# CHIP_tzatziffy_v7.net
KiCad netlist of a schematic drawn in EAGLE
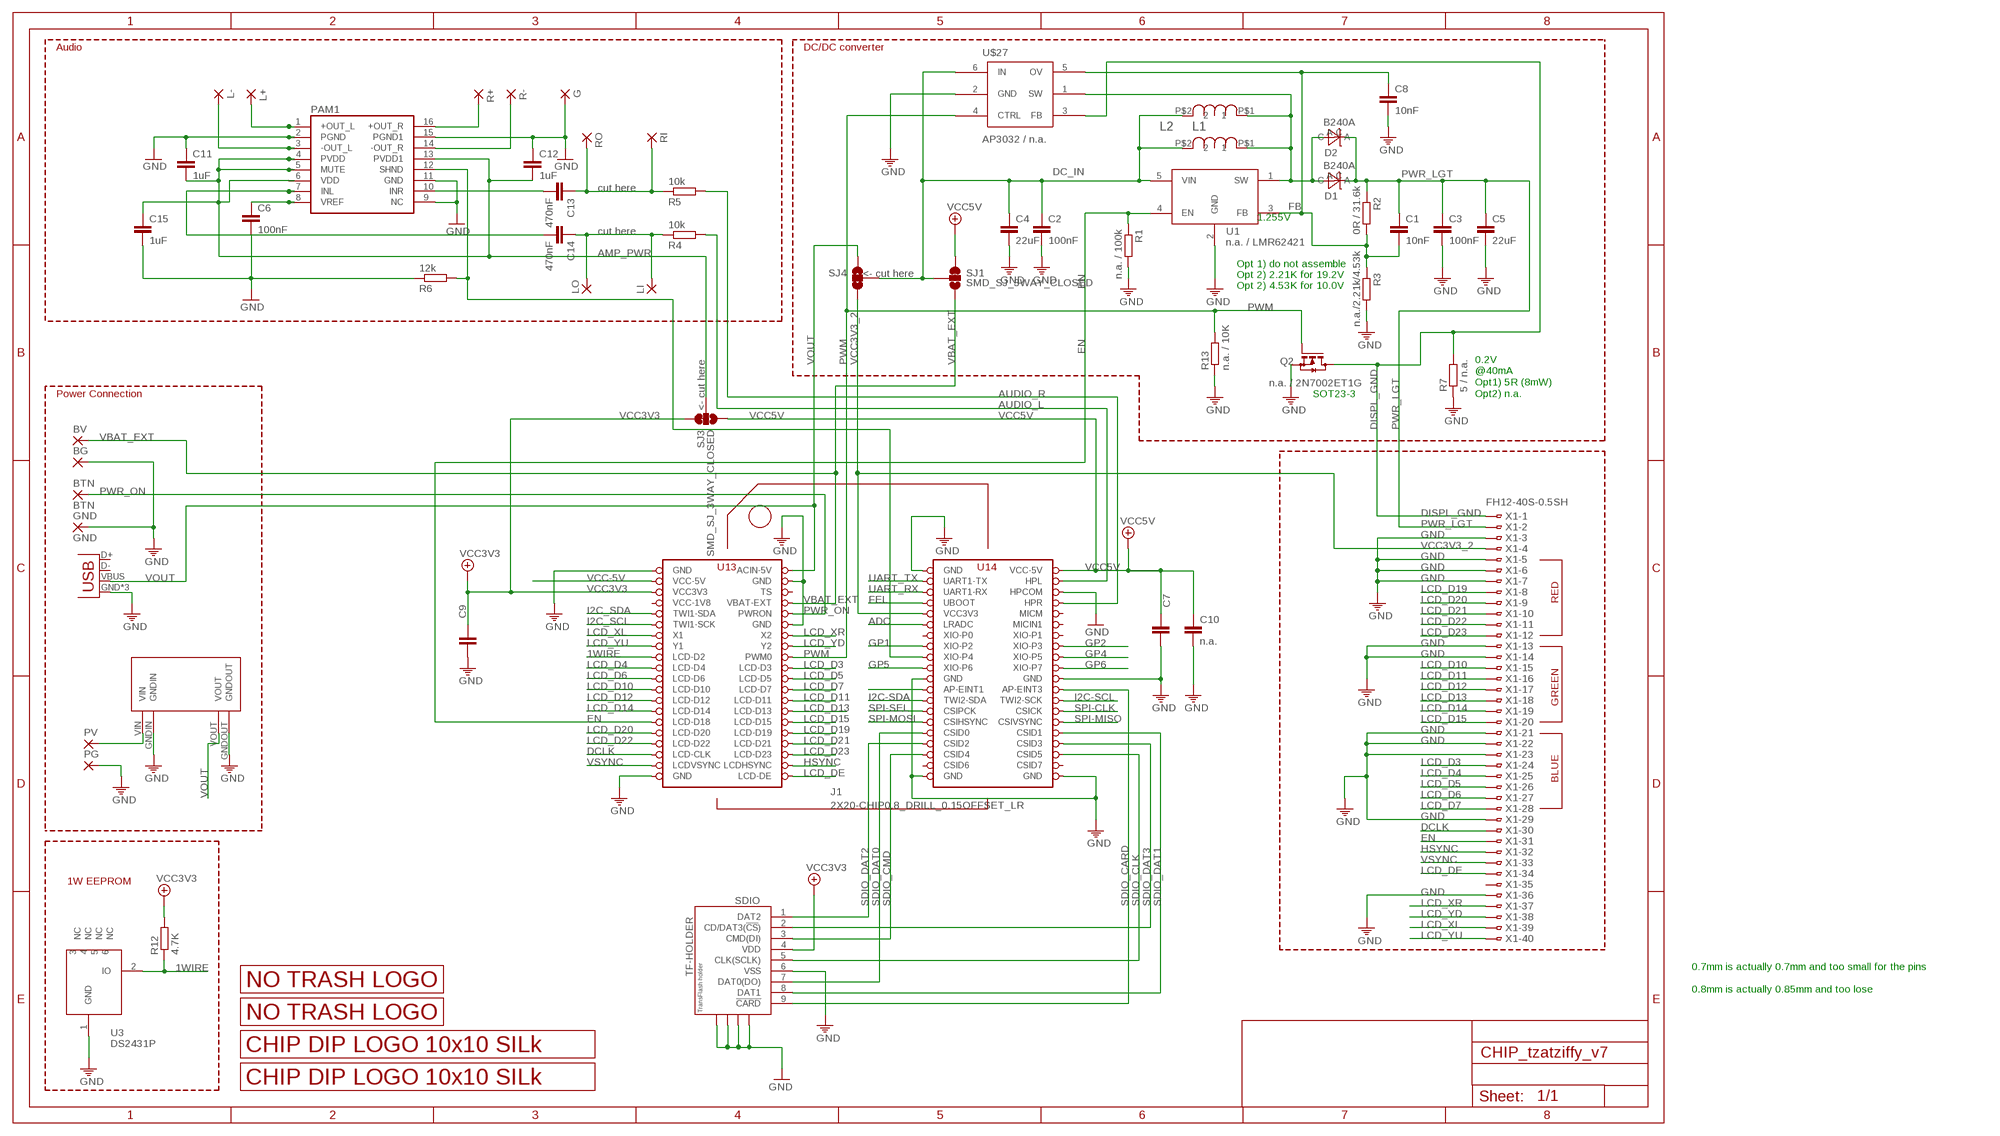
[diagram p0: schematic, sheet 1]

(export (version "E")
  (design (tool "Eeschema 10.0.6"))
  (components
    (comp (ref "BG")
      (value "1,6/0,8")
      (footprint "eagle-import:1,6_0,8")
      (libsource (lib "eagle-import") (part "1,6/0,8"))
    )
    (comp (ref "BTN")
      (value "BTN")
      (footprint "eagle-import:SMD1,27-2,54")
      (libsource (lib "eagle-import") (part "SMD2"))
    )
    (comp (ref "BV")
      (value "1,6/0,8")
      (footprint "eagle-import:1,6_0,8")
      (libsource (lib "eagle-import") (part "1,6/0,8"))
    )
    (comp (ref "C1")
      (value "10nF")
      (footprint "eagle-import:C0805")
      (libsource (lib "eagle-import") (part "C-EUC0805"))
    )
    (comp (ref "C2")
      (value "100nF")
      (footprint "eagle-import:C0805")
      (libsource (lib "eagle-import") (part "C-EUC0805"))
    )
    (comp (ref "C3")
      (value "100nF")
      (footprint "eagle-import:C0805")
      (libsource (lib "eagle-import") (part "C-EUC0805"))
    )
    (comp (ref "C4")
      (value "22uF")
      (footprint "eagle-import:C1206")
      (libsource (lib "eagle-import") (part "C-EUC1206"))
    )
    (comp (ref "C5")
      (value "22uF")
      (footprint "eagle-import:C1206")
      (libsource (lib "eagle-import") (part "C-EUC1206"))
    )
    (comp (ref "C6")
      (value "100nF")
      (footprint "eagle-import:C0805")
      (libsource (lib "eagle-import") (part "C-EUC0805"))
    )
    (comp (ref "C7")
      (value "n.a.")
      (footprint "eagle-import:C0805")
      (libsource (lib "eagle-import") (part "C-EUC0805"))
    )
    (comp (ref "C8")
      (value "10nF")
      (footprint "eagle-import:C0805")
      (libsource (lib "eagle-import") (part "C-EUC0805"))
    )
    (comp (ref "C9")
      (value "n.a.")
      (footprint "eagle-import:C0805")
      (libsource (lib "eagle-import") (part "C-EUC0805"))
    )
    (comp (ref "C10")
      (value "n.a.")
      (footprint "eagle-import:C0805")
      (libsource (lib "eagle-import") (part "C-EUC0805"))
    )
    (comp (ref "C11")
      (value "1uF")
      (footprint "eagle-import:C0805")
      (libsource (lib "eagle-import") (part "C-EUC0805"))
    )
    (comp (ref "C12")
      (value "1uF")
      (footprint "eagle-import:C0805")
      (libsource (lib "eagle-import") (part "C-EUC0805"))
    )
    (comp (ref "C13")
      (value "470nF")
      (footprint "eagle-import:C0805")
      (libsource (lib "eagle-import") (part "C-EUC0805"))
    )
    (comp (ref "C14")
      (value "470nF")
      (footprint "eagle-import:C0805")
      (libsource (lib "eagle-import") (part "C-EUC0805"))
    )
    (comp (ref "C15")
      (value "1uF")
      (footprint "eagle-import:C0805")
      (libsource (lib "eagle-import") (part "C-EUC0805"))
    )
    (comp (ref "D1")
      (value "B240A")
      (footprint "eagle-import:DO-214AC")
      (fields (field (name "MFG") "DIGIKEY") (field (name "VENDOR_PART_NUMBER") "B240A-13-F"))
      (libsource (lib "eagle-import") (part "DIODE_SCHTKY_B240"))
    )
    (comp (ref "D2")
      (value "B240A")
      (footprint "eagle-import:DO-214AC")
      (fields (field (name "MFG") "DIGIKEY") (field (name "VENDOR_PART_NUMBER") "B240A-13-F"))
      (libsource (lib "eagle-import") (part "DIODE_SCHTKY_B240"))
    )
    (comp (ref "G")
      (value "1,6/0,8")
      (footprint "eagle-import:1,6_0,8")
      (libsource (lib "eagle-import") (part "1,6/0,8"))
    )
    (comp (ref "GND")
      (value "GND")
      (footprint "eagle-import:SMD1,27-2,54")
      (libsource (lib "eagle-import") (part "SMD2"))
    )
    (comp (ref "J1")
      (value "2X20-CHIP0.8_DRILL_0.15OFFSET_LR")
      (footprint "eagle-import:2X20CHIP_0.15MM_OFFSET_TH_08")
      (libsource (lib "eagle-import") (part "2X20-CHIP0.8_DRILL_0.15OFFSET_LR"))
    )
    (comp (ref "L+")
      (value "1,6/0,8")
      (footprint "eagle-import:1,6_0,8")
      (libsource (lib "eagle-import") (part "1,6/0,8"))
    )
    (comp (ref "L-")
      (value "1,6/0,8")
      (footprint "eagle-import:1,6_0,8")
      (libsource (lib "eagle-import") (part "1,6/0,8"))
    )
    (comp (ref "L1")
      (value "SRN6045-100M")
      (footprint "eagle-import:SRN6045")
      (fields (field (name "MFG") "DIGIKEY"))
      (libsource (lib "eagle-import") (part "SRN6045-100M"))
    )
    (comp (ref "L2")
      (value "SRN6045-100M")
      (footprint "eagle-import:SRN6045")
      (fields (field (name "MFG") "DIGIKEY"))
      (libsource (lib "eagle-import") (part "SRN6045-100M"))
    )
    (comp (ref "LI")
      (value "1,6/0,8")
      (footprint "eagle-import:1,6_0,8")
      (libsource (lib "eagle-import") (part "1,6/0,8"))
    )
    (comp (ref "LO")
      (value "1,6/0,8")
      (footprint "eagle-import:1,6_0,8")
      (libsource (lib "eagle-import") (part "1,6/0,8"))
    )
    (comp (ref "PAM1")
      (value "PAM8403")
      (footprint "eagle-import:SOP-16")
      (libsource (lib "eagle-import") (part "PAM8403"))
    )
    (comp (ref "PG")
      (value "1,6/0,8")
      (footprint "eagle-import:1,6_0,8")
      (libsource (lib "eagle-import") (part "1,6/0,8"))
    )
    (comp (ref "PV")
      (value "1,6/0,8")
      (footprint "eagle-import:1,6_0,8")
      (libsource (lib "eagle-import") (part "1,6/0,8"))
    )
    (comp (ref "Q2")
      (value "n.a. / 2N7002ET1G")
      (footprint "eagle-import:SOT23")
      (libsource (lib "eagle-import") (part "BSS123"))
    )
    (comp (ref "R+")
      (value "1,6/0,8")
      (footprint "eagle-import:1,6_0,8")
      (libsource (lib "eagle-import") (part "1,6/0,8"))
    )
    (comp (ref "R-")
      (value "1,6/0,8")
      (footprint "eagle-import:1,6_0,8")
      (libsource (lib "eagle-import") (part "1,6/0,8"))
    )
    (comp (ref "R1")
      (value "n.a. / 100k")
      (footprint "eagle-import:M0805")
      (libsource (lib "eagle-import") (part "R-EU_M0805"))
    )
    (comp (ref "R2")
      (value "0R / 31.6k")
      (footprint "eagle-import:M0805")
      (libsource (lib "eagle-import") (part "R-EU_M0805"))
    )
    (comp (ref "R3")
      (value "n.a./2.21k/4.53k")
      (footprint "eagle-import:M0805")
      (libsource (lib "eagle-import") (part "R-EU_M0805"))
    )
    (comp (ref "R4")
      (value "10k")
      (footprint "eagle-import:R0805")
      (libsource (lib "eagle-import") (part "R-EU_R0805"))
    )
    (comp (ref "R5")
      (value "10k")
      (footprint "eagle-import:R0805")
      (libsource (lib "eagle-import") (part "R-EU_R0805"))
    )
    (comp (ref "R6")
      (value "12k")
      (footprint "eagle-import:R0805")
      (libsource (lib "eagle-import") (part "R-EU_R0805"))
    )
    (comp (ref "R7")
      (value "5 / n.a.")
      (footprint "eagle-import:M0805")
      (libsource (lib "eagle-import") (part "R-EU_M0805"))
    )
    (comp (ref "R12")
      (value "4.7K")
      (footprint "eagle-import:M0805")
      (libsource (lib "eagle-import") (part "R-EU_M0805"))
    )
    (comp (ref "R13")
      (value "n.a. / 10K")
      (footprint "eagle-import:M0805")
      (libsource (lib "eagle-import") (part "R-EU_M0805"))
    )
    (comp (ref "RI")
      (value "1,6/0,8")
      (footprint "eagle-import:1,6_0,8")
      (libsource (lib "eagle-import") (part "1,6/0,8"))
    )
    (comp (ref "RO")
      (value "1,6/0,8")
      (footprint "eagle-import:1,6_0,8")
      (libsource (lib "eagle-import") (part "1,6/0,8"))
    )
    (comp (ref "SDIO")
      (value "TF-HOLDER")
      (footprint "eagle-import:TF-PULL")
      (libsource (lib "eagle-import") (part "TF-HOLDER"))
    )
    (comp (ref "SJ1")
      (value "SMD_SJ_3WAY_CLOSED")
      (footprint "eagle-import:SMD_SJ_3WAY_CLOSED")
      (libsource (lib "eagle-import") (part "SMD_SJ_3WAY_CLOSED"))
    )
    (comp (ref "SJ3")
      (value "SMD_SJ_3WAY_CLOSED")
      (footprint "eagle-import:SMD_SJ_3WAY_CLOSED")
      (libsource (lib "eagle-import") (part "SMD_SJ_3WAY_CLOSED"))
    )
    (comp (ref "SJ4")
      (value "SMD_SJ_3WAY_OPENT")
      (footprint "eagle-import:SMD_SJ_3WAY_OPEN")
      (libsource (lib "eagle-import") (part "SMD_SJ_3WAY_OPENT"))
    )
    (comp (ref "U$2")
      (value "LOGO_10X10_SILK")
      (footprint "eagle-import:LOGO2_10X10_SILK")
      (libsource (lib "eagle-import") (part "LOGO_10X10_SILK"))
    )
    (comp (ref "U$3")
      (value "LOGO_NO_TRASHROHS")
      (footprint "eagle-import:LOGO_ROHS_SYM")
      (libsource (lib "eagle-import") (part "LOGO_NO_TRASHROHS"))
    )
    (comp (ref "U$4")
      (value "LOGO_NO_TRASHNO_TRASH")
      (footprint "eagle-import:LOGO_ROHS_NO_TRASH")
      (libsource (lib "eagle-import") (part "LOGO_NO_TRASHNO_TRASH"))
    )
    (comp (ref "U$5")
      (value "LOGO_10X10_SILK")
      (footprint "eagle-import:LOGO2_10X10_SILK")
      (libsource (lib "eagle-import") (part "LOGO_10X10_SILK"))
    )
    (comp (ref "U$10")
      (value "MP1584EN_FRAMELESS")
      (footprint "eagle-import:MP1584EN_FRAMELESS")
      (libsource (lib "eagle-import") (part "MP1584EN_FRAMELESS"))
    )
    (comp (ref "U$27")
      (value "AP3032 / n.a.")
      (footprint "eagle-import:SOT23-6")
      (libsource (lib "eagle-import") (part "AP3032"))
    )
    (comp (ref "U1")
      (value "n.a. / LMR62421")
      (footprint "eagle-import:SOT23-5")
      (fields (field (name "MFG") "DIGIKEY") (field (name "VENDOR_PART_NUMBER") "LMR62421XMFE/NOPB"))
      (libsource (lib "eagle-import") (part "LMR62421"))
    )
    (comp (ref "U3")
      (value "DS2431P")
      (footprint "eagle-import:TSOC6")
      (fields (field (name "MFG") "DIGIKEY") (field (name "VENDOR_PART_NUMBER") "DS2431P+T&R"))
      (libsource (lib "eagle-import") (part "DS2431P"))
    )
    (comp (ref "USB")
      (value "USBUSB-MICROB-SMT-DIP")
      (footprint "eagle-import:USB-MICROB-SMT-DIP")
      (libsource (lib "eagle-import") (part "USBUSB-MICROB-SMT-DIP"))
    )
    (comp (ref "X1")
      (value "FH12-40S-0.5SH")
      (footprint "eagle-import:FH12-40S-0.5SH")
      (fields (field (name "MFG") "DIGIKEY") (field (name "VENDOR_PART_NUMBER") "FH12-40S-0.5SH(55)"))
      (libsource (lib "eagle-import") (part "FH12-40S-0.5SH"))
    )
  )
  (nets
    (net (code "1") (name "/1WIRE") (class "Default")
      (node (ref "J1") (pin "LCD-D2") (pinfunction "LCD-D2_LCD-D2") (pintype "passive"))
      (node (ref "R12") (pin "1") (pinfunction "1_1") (pintype "passive"))
      (node (ref "U3") (pin "2") (pinfunction "IO_2") (pintype "bidirectional"))
    )
    (net (code "2") (name "/ADC") (class "Default")
      (node (ref "J1") (pin "LRADC") (pinfunction "LRADC_LRADC") (pintype "passive"))
    )
    (net (code "3") (name "/AMP_PWR") (class "Default")
      (node (ref "C11") (pin "2") (pinfunction "2_2") (pintype "passive"))
      (node (ref "C12") (pin "2") (pinfunction "2_2") (pintype "passive"))
      (node (ref "C15") (pin "1") (pinfunction "1_1") (pintype "passive"))
      (node (ref "PAM1") (pin "13") (pinfunction "PVDD1_13") (pintype "output"))
      (node (ref "PAM1") (pin "4") (pinfunction "PVDD_4") (pintype "input"))
      (node (ref "PAM1") (pin "5") (pinfunction "MUTE_5") (pintype "input"))
      (node (ref "PAM1") (pin "6") (pinfunction "VDD_6") (pintype "input"))
      (node (ref "SJ3") (pin "2") (pinfunction "2_2") (pintype "passive"))
    )
    (net (code "4") (name "/AUDIO_L") (class "Default")
      (node (ref "J1") (pin "HPL") (pinfunction "HPL_HPL") (pintype "passive"))
      (node (ref "R4") (pin "2") (pinfunction "2_2") (pintype "passive"))
    )
    (net (code "5") (name "/AUDIO_R") (class "Default")
      (node (ref "J1") (pin "HPR") (pinfunction "HPR_HPR") (pintype "passive"))
      (node (ref "R5") (pin "2") (pinfunction "2_2") (pintype "passive"))
    )
    (net (code "6") (name "/DCLK") (class "Default")
      (node (ref "J1") (pin "LCD-CLK") (pinfunction "LCD-CLK_LCD-CLK") (pintype "passive"))
      (node (ref "X1") (pin "30") (pinfunction "1_30") (pintype "passive"))
    )
    (net (code "7") (name "/DC_IN") (class "Default")
      (node (ref "C2") (pin "1") (pinfunction "1_1") (pintype "passive"))
      (node (ref "C4") (pin "1") (pinfunction "1_1") (pintype "passive"))
      (node (ref "L1") (pin "P$2") (pinfunction "2_P$2") (pintype "passive"))
      (node (ref "L2") (pin "P$2") (pinfunction "2_P$2") (pintype "passive"))
      (node (ref "SJ1") (pin "2") (pinfunction "2_2") (pintype "passive"))
      (node (ref "SJ4") (pin "2") (pinfunction "2_2") (pintype "passive"))
      (node (ref "U$27") (pin "6") (pinfunction "IN_6") (pintype "power_in"))
      (node (ref "U1") (pin "5") (pinfunction "VIN_5") (pintype "bidirectional"))
    )
    (net (code "8") (name "/DISPL_GND") (class "Default")
      (node (ref "Q2") (pin "3") (pinfunction "D_3") (pintype "passive"))
      (node (ref "R7") (pin "2") (pinfunction "2_2") (pintype "passive"))
      (node (ref "U$27") (pin "3") (pinfunction "FB_3") (pintype "passive"))
      (node (ref "X1") (pin "1") (pinfunction "1_1") (pintype "passive"))
    )
    (net (code "9") (name "/EN") (class "Default")
      (node (ref "J1") (pin "LCD-D18") (pinfunction "LCD-D18_LCD-D18") (pintype "passive"))
      (node (ref "R1") (pin "1") (pinfunction "1_1") (pintype "passive"))
      (node (ref "U1") (pin "4") (pinfunction "EN_4") (pintype "bidirectional"))
      (node (ref "X1") (pin "31") (pinfunction "1_31") (pintype "passive"))
    )
    (net (code "10") (name "/FB") (class "Default")
      (node (ref "C1") (pin "2") (pinfunction "2_2") (pintype "passive"))
      (node (ref "C8") (pin "1") (pinfunction "1_1") (pintype "passive"))
      (node (ref "R2") (pin "2") (pinfunction "2_2") (pintype "passive"))
      (node (ref "R3") (pin "1") (pinfunction "1_1") (pintype "passive"))
      (node (ref "U$27") (pin "5") (pinfunction "OV_5") (pintype "power_in"))
      (node (ref "U1") (pin "3") (pinfunction "FB_3") (pintype "bidirectional"))
    )
    (net (code "11") (name "/FEL") (class "Default")
      (node (ref "J1") (pin "FEL") (pinfunction "UBOOT_FEL") (pintype "passive"))
    )
    (net (code "12") (name "/GP1") (class "Default")
      (node (ref "J1") (pin "XIO-P2") (pinfunction "XIO-P2_XIO-P2") (pintype "passive"))
    )
    (net (code "13") (name "/GP2") (class "Default")
      (node (ref "J1") (pin "XIO-P3") (pinfunction "XIO-P3_XIO-P3") (pintype "passive"))
    )
    (net (code "14") (name "/GP4") (class "Default")
      (node (ref "J1") (pin "XIO-P5") (pinfunction "XIO-P5_XIO-P5") (pintype "passive"))
    )
    (net (code "15") (name "/GP5") (class "Default")
      (node (ref "J1") (pin "XIO-P6") (pinfunction "XIO-P6_XIO-P6") (pintype "passive"))
    )
    (net (code "16") (name "/GP6") (class "Default")
      (node (ref "J1") (pin "XIO-P7") (pinfunction "XIO-P7_XIO-P7") (pintype "passive"))
    )
    (net (code "17") (name "/HSYNC") (class "Default")
      (node (ref "J1") (pin "LCD-HSYNC") (pinfunction "LCDHSYNC_LCD-HSYNC") (pintype "passive"))
      (node (ref "X1") (pin "32") (pinfunction "1_32") (pintype "passive"))
    )
    (net (code "18") (name "/I2C-SCL") (class "Default")
      (node (ref "J1") (pin "TWI2-SCK") (pinfunction "TWI2-SCK_TWI2-SCK") (pintype "passive"))
    )
    (net (code "19") (name "/I2C-SDA") (class "Default")
      (node (ref "J1") (pin "TWI2-SDA") (pinfunction "TWI2-SDA_TWI2-SDA") (pintype "passive"))
    )
    (net (code "20") (name "/I2C_SCL") (class "Default")
      (node (ref "J1") (pin "TWI1-SCK") (pinfunction "TWI1-SCK_TWI1-SCK") (pintype "passive"))
    )
    (net (code "21") (name "/I2C_SDA") (class "Default")
      (node (ref "J1") (pin "TWI1-SDA") (pinfunction "TWI1-SDA_TWI1-SDA") (pintype "passive"))
    )
    (net (code "22") (name "/LCD_D3") (class "Default")
      (node (ref "J1") (pin "LCD-D3") (pinfunction "LCD-D3_LCD-D3") (pintype "passive"))
      (node (ref "X1") (pin "24") (pinfunction "1_24") (pintype "passive"))
    )
    (net (code "23") (name "/LCD_D4") (class "Default")
      (node (ref "J1") (pin "LCD-D4") (pinfunction "LCD-D4_LCD-D4") (pintype "passive"))
      (node (ref "X1") (pin "25") (pinfunction "1_25") (pintype "passive"))
    )
    (net (code "24") (name "/LCD_D5") (class "Default")
      (node (ref "J1") (pin "LCD-D5") (pinfunction "LCD-D5_LCD-D5") (pintype "passive"))
      (node (ref "X1") (pin "26") (pinfunction "1_26") (pintype "passive"))
    )
    (net (code "25") (name "/LCD_D6") (class "Default")
      (node (ref "J1") (pin "LCD-D6") (pinfunction "LCD-D6_LCD-D6") (pintype "passive"))
      (node (ref "X1") (pin "27") (pinfunction "1_27") (pintype "passive"))
    )
    (net (code "26") (name "/LCD_D7") (class "Default")
      (node (ref "J1") (pin "LCD-D7") (pinfunction "LCD-D7_LCD-D7") (pintype "passive"))
      (node (ref "X1") (pin "28") (pinfunction "1_28") (pintype "passive"))
    )
    (net (code "27") (name "/LCD_D10") (class "Default")
      (node (ref "J1") (pin "LCD-D10") (pinfunction "LCD-D10_LCD-D10") (pintype "passive"))
      (node (ref "X1") (pin "15") (pinfunction "1_15") (pintype "passive"))
    )
    (net (code "28") (name "/LCD_D11") (class "Default")
      (node (ref "J1") (pin "LCD-D11") (pinfunction "LCD-D11_LCD-D11") (pintype "passive"))
      (node (ref "X1") (pin "16") (pinfunction "1_16") (pintype "passive"))
    )
    (net (code "29") (name "/LCD_D12") (class "Default")
      (node (ref "J1") (pin "LCD-D12") (pinfunction "LCD-D12_LCD-D12") (pintype "passive"))
      (node (ref "X1") (pin "17") (pinfunction "1_17") (pintype "passive"))
    )
    (net (code "30") (name "/LCD_D13") (class "Default")
      (node (ref "J1") (pin "LCD-D13") (pinfunction "LCD-D13_LCD-D13") (pintype "passive"))
      (node (ref "X1") (pin "18") (pinfunction "1_18") (pintype "passive"))
    )
    (net (code "31") (name "/LCD_D14") (class "Default")
      (node (ref "J1") (pin "LCD-D14") (pinfunction "LCD-D14_LCD-D14") (pintype "passive"))
      (node (ref "X1") (pin "19") (pinfunction "1_19") (pintype "passive"))
    )
    (net (code "32") (name "/LCD_D15") (class "Default")
      (node (ref "J1") (pin "LCD-D15") (pinfunction "LCD-D15_LCD-D15") (pintype "passive"))
      (node (ref "X1") (pin "20") (pinfunction "1_20") (pintype "passive"))
    )
    (net (code "33") (name "/LCD_D19") (class "Default")
      (node (ref "J1") (pin "LCD-D19") (pinfunction "LCD-D19_LCD-D19") (pintype "passive"))
      (node (ref "X1") (pin "8") (pinfunction "1_8") (pintype "passive"))
    )
    (net (code "34") (name "/LCD_D20") (class "Default")
      (node (ref "J1") (pin "LCD-D20") (pinfunction "LCD-D20_LCD-D20") (pintype "passive"))
      (node (ref "X1") (pin "9") (pinfunction "1_9") (pintype "passive"))
    )
    (net (code "35") (name "/LCD_D21") (class "Default")
      (node (ref "J1") (pin "LCD-D21") (pinfunction "LCD-D21_LCD-D21") (pintype "passive"))
      (node (ref "X1") (pin "10") (pinfunction "1_10") (pintype "passive"))
    )
    (net (code "36") (name "/LCD_D22") (class "Default")
      (node (ref "J1") (pin "LCD-D22") (pinfunction "LCD-D22_LCD-D22") (pintype "passive"))
      (node (ref "X1") (pin "11") (pinfunction "1_11") (pintype "passive"))
    )
    (net (code "37") (name "/LCD_D23") (class "Default")
      (node (ref "J1") (pin "LCD-D23") (pinfunction "LCD-D23_LCD-D23") (pintype "passive"))
      (node (ref "X1") (pin "12") (pinfunction "1_12") (pintype "passive"))
    )
    (net (code "38") (name "/LCD_DE") (class "Default")
      (node (ref "J1") (pin "LCD-DE") (pinfunction "LCD-DE_LCD-DE") (pintype "passive"))
      (node (ref "X1") (pin "34") (pinfunction "1_34") (pintype "passive"))
    )
    (net (code "39") (name "/LCD_XL") (class "Default")
      (node (ref "J1") (pin "X1") (pinfunction "X1_X1") (pintype "passive"))
      (node (ref "X1") (pin "39") (pinfunction "1_39") (pintype "passive"))
    )
    (net (code "40") (name "/LCD_XR") (class "Default")
      (node (ref "J1") (pin "X2") (pinfunction "X2_X2") (pintype "passive"))
      (node (ref "X1") (pin "37") (pinfunction "1_37") (pintype "passive"))
    )
    (net (code "41") (name "/LCD_YD") (class "Default")
      (node (ref "J1") (pin "Y2") (pinfunction "Y2_Y2") (pintype "passive"))
      (node (ref "X1") (pin "38") (pinfunction "1_38") (pintype "passive"))
    )
    (net (code "42") (name "/LCD_YU") (class "Default")
      (node (ref "J1") (pin "Y1") (pinfunction "Y1_Y1") (pintype "passive"))
      (node (ref "X1") (pin "40") (pinfunction "1_40") (pintype "passive"))
    )
    (net (code "43") (name "/PWM") (class "Default")
      (node (ref "J1") (pin "PWM0") (pinfunction "PWM0_PWM0") (pintype "passive"))
      (node (ref "Q2") (pin "1") (pinfunction "G_1") (pintype "passive"))
      (node (ref "R13") (pin "2") (pinfunction "2_2") (pintype "passive"))
      (node (ref "U$27") (pin "4") (pinfunction "CTRL_4") (pintype "input"))
    )
    (net (code "44") (name "/PWR_LGT") (class "Default")
      (node (ref "C1") (pin "1") (pinfunction "1_1") (pintype "passive"))
      (node (ref "C3") (pin "1") (pinfunction "1_1") (pintype "passive"))
      (node (ref "C5") (pin "1") (pinfunction "1_1") (pintype "passive"))
      (node (ref "D1") (pin "C") (pinfunction "C_C") (pintype "bidirectional"))
      (node (ref "D2") (pin "C") (pinfunction "C_C") (pintype "bidirectional"))
      (node (ref "R2") (pin "1") (pinfunction "1_1") (pintype "passive"))
      (node (ref "X1") (pin "2") (pinfunction "1_2") (pintype "passive"))
    )
    (net (code "45") (name "/PWR_ON") (class "Default")
      (node (ref "BTN") (pin "1") (pinfunction "P_1") (pintype "passive"))
      (node (ref "J1") (pin "PWRON") (pinfunction "PWRON_PWRON") (pintype "passive"))
    )
    (net (code "46") (name "/SDIO_CARD") (class "Default")
      (node (ref "J1") (pin "AP-EINT3") (pinfunction "AP-EINT3_AP-EINT3") (pintype "passive"))
      (node (ref "SDIO") (pin "9") (pinfunction "~{CARD}_9") (pintype "passive"))
    )
    (net (code "47") (name "/SDIO_CLK") (class "Default")
      (node (ref "J1") (pin "CSID5") (pinfunction "CSID5_CSID5") (pintype "passive"))
      (node (ref "SDIO") (pin "5") (pinfunction "CLK(SCLK)_5") (pintype "input"))
    )
    (net (code "48") (name "/SDIO_CMD") (class "Default")
      (node (ref "J1") (pin "CSID4") (pinfunction "CSID4_CSID4") (pintype "passive"))
      (node (ref "SDIO") (pin "3") (pinfunction "CMD(DI)_3") (pintype "bidirectional"))
    )
    (net (code "49") (name "/SDIO_DAT0") (class "Default")
      (node (ref "J1") (pin "CSID0") (pinfunction "CSID0_CSID0") (pintype "passive"))
      (node (ref "SDIO") (pin "7") (pinfunction "DAT0(DO)_7") (pintype "bidirectional"))
    )
    (net (code "50") (name "/SDIO_DAT1") (class "Default")
      (node (ref "J1") (pin "CSID1") (pinfunction "CSID1_CSID1") (pintype "passive"))
      (node (ref "SDIO") (pin "8") (pinfunction "DAT1_8") (pintype "bidirectional"))
    )
    (net (code "51") (name "/SDIO_DAT2") (class "Default")
      (node (ref "J1") (pin "CSID2") (pinfunction "CSID2_CSID2") (pintype "passive"))
      (node (ref "SDIO") (pin "1") (pinfunction "DAT2_1") (pintype "bidirectional"))
    )
    (net (code "52") (name "/SDIO_DAT3") (class "Default")
      (node (ref "J1") (pin "CSID3") (pinfunction "CSID3_CSID3") (pintype "passive"))
      (node (ref "SDIO") (pin "2") (pinfunction "CD/DAT3(~{CS})_2") (pintype "bidirectional"))
    )
    (net (code "53") (name "/SPI-CLK") (class "Default")
      (node (ref "J1") (pin "CSICK") (pinfunction "CSICK_CSICK") (pintype "passive"))
    )
    (net (code "54") (name "/SPI-MISO") (class "Default")
      (node (ref "J1") (pin "CSIVSYNC") (pinfunction "CSIVSYNC_CSIVSYNC") (pintype "passive"))
    )
    (net (code "55") (name "/SPI-MOSI") (class "Default")
      (node (ref "J1") (pin "CSIHSYNC") (pinfunction "CSIHSYNC_CSIHSYNC") (pintype "passive"))
    )
    (net (code "56") (name "/SPI-SEL") (class "Default")
      (node (ref "J1") (pin "CSIPCK") (pinfunction "CSIPCK_CSIPCK") (pintype "passive"))
    )
    (net (code "57") (name "/UART_RX") (class "Default")
      (node (ref "J1") (pin "UART1-RX") (pinfunction "UART1-RX_UART1-RX") (pintype "passive"))
    )
    (net (code "58") (name "/UART_TX") (class "Default")
      (node (ref "J1") (pin "UART1-TX") (pinfunction "UART1-TX_UART1-TX") (pintype "passive"))
    )
    (net (code "59") (name "/VBAT_EXT") (class "Default")
      (node (ref "BV") (pin "1") (pinfunction "P_1") (pintype "passive"))
      (node (ref "J1") (pin "BAT") (pinfunction "VBAT-EXT_BAT") (pintype "passive"))
      (node (ref "SJ1") (pin "3") (pinfunction "3_3") (pintype "passive"))
    )
    (net (code "60") (name "/VCC-1V8") (class "Default")
      (node (ref "J1") (pin "VCC1V8") (pinfunction "VCC-1V8_VCC1V8") (pintype "power_in"))
    )
    (net (code "61") (name "/VCC-5V") (class "Default")
      (node (ref "J1") (pin "VCC5V@0") (pinfunction "VCC-5V_VCC5V@0") (pintype "power_in"))
    )
    (net (code "62") (name "/VCC3V3_2") (class "Default")
      (node (ref "J1") (pin "VCC3V3@1") (pinfunction "VCC3V3_VCC3V3@1") (pintype "power_in"))
      (node (ref "SJ4") (pin "3") (pinfunction "3_3") (pintype "passive"))
      (node (ref "X1") (pin "4") (pinfunction "1_4") (pintype "passive"))
    )
    (net (code "63") (name "/VOUT") (class "Default")
      (node (ref "J1") (pin "CHG-IN") (pinfunction "ACIN-5V_CHG-IN") (pintype "passive"))
      (node (ref "SJ4") (pin "1") (pinfunction "1_1") (pintype "passive"))
      (node (ref "U$10") (pin "VOUT") (pinfunction "VOUT_VOUT") (pintype "power_in"))
      (node (ref "USB") (pin "VBUS") (pinfunction "VBUS_VBUS") (pintype "bidirectional"))
    )
    (net (code "64") (name "/VSYNC") (class "Default")
      (node (ref "J1") (pin "LCD-VSYNC") (pinfunction "LCDVSYNC_LCD-VSYNC") (pintype "passive"))
      (node (ref "X1") (pin "33") (pinfunction "1_33") (pintype "passive"))
    )
    (net (code "65") (name "GND") (class "Default")
      (node (ref "BG") (pin "1") (pinfunction "P_1") (pintype "passive"))
      (node (ref "C10") (pin "2") (pinfunction "2_2") (pintype "passive"))
      (node (ref "C11") (pin "1") (pinfunction "1_1") (pintype "passive"))
      (node (ref "C12") (pin "1") (pinfunction "1_1") (pintype "passive"))
      (node (ref "C15") (pin "2") (pinfunction "2_2") (pintype "passive"))
      (node (ref "C2") (pin "2") (pinfunction "2_2") (pintype "passive"))
      (node (ref "C3") (pin "2") (pinfunction "2_2") (pintype "passive"))
      (node (ref "C4") (pin "2") (pinfunction "2_2") (pintype "passive"))
      (node (ref "C5") (pin "2") (pinfunction "2_2") (pintype "passive"))
      (node (ref "C6") (pin "2") (pinfunction "2_2") (pintype "passive"))
      (node (ref "C7") (pin "2") (pinfunction "2_2") (pintype "passive"))
      (node (ref "C8") (pin "2") (pinfunction "2_2") (pintype "passive"))
      (node (ref "C9") (pin "2") (pinfunction "2_2") (pintype "passive"))
      (node (ref "G") (pin "1") (pinfunction "P_1") (pintype "passive"))
      (node (ref "GND") (pin "1") (pinfunction "P_1") (pintype "passive"))
      (node (ref "J1") (pin "GND@1") (pinfunction "GND_GND@1") (pintype "power_in"))
      (node (ref "J1") (pin "GND@10") (pinfunction "GND_GND@10") (pintype "power_in"))
      (node (ref "J1") (pin "GND@2") (pinfunction "GND_GND@2") (pintype "power_in"))
      (node (ref "J1") (pin "GND@3") (pinfunction "GND_GND@3") (pintype "power_in"))
      (node (ref "J1") (pin "GND@4") (pinfunction "GND_GND@4") (pintype "power_in"))
      (node (ref "J1") (pin "GND@5") (pinfunction "GND_GND@5") (pintype "power_in"))
      (node (ref "J1") (pin "GND@6") (pinfunction "GND_GND@6") (pintype "power_in"))
      (node (ref "J1") (pin "GND@7") (pinfunction "GND_GND@7") (pintype "power_in"))
      (node (ref "J1") (pin "GND@8") (pinfunction "GND_GND@8") (pintype "power_in"))
      (node (ref "J1") (pin "HPCOM") (pinfunction "HPCOM_HPCOM") (pintype "passive"))
      (node (ref "PAM1") (pin "11") (pinfunction "GND_11") (pintype "output"))
      (node (ref "PAM1") (pin "15") (pinfunction "PGND1_15") (pintype "output"))
      (node (ref "PAM1") (pin "2") (pinfunction "PGND_2") (pintype "input"))
      (node (ref "PAM1") (pin "9") (pinfunction "NC_9") (pintype "output"))
      (node (ref "PG") (pin "1") (pinfunction "P_1") (pintype "passive"))
      (node (ref "Q2") (pin "2") (pinfunction "S_2") (pintype "passive"))
      (node (ref "R1") (pin "2") (pinfunction "2_2") (pintype "passive"))
      (node (ref "R13") (pin "1") (pinfunction "1_1") (pintype "passive"))
      (node (ref "R3") (pin "2") (pinfunction "2_2") (pintype "passive"))
      (node (ref "R6") (pin "1") (pinfunction "1_1") (pintype "passive"))
      (node (ref "R7") (pin "1") (pinfunction "1_1") (pintype "passive"))
      (node (ref "SDIO") (pin "6") (pinfunction "VSS_6") (pintype "power_in"))
      (node (ref "SDIO") (pin "S1") (pinfunction "S1_S1") (pintype "passive"))
      (node (ref "SDIO") (pin "S2") (pinfunction "S2_S2") (pintype "passive"))
      (node (ref "SDIO") (pin "S3") (pinfunction "S3_S3") (pintype "passive"))
      (node (ref "SDIO") (pin "S4") (pinfunction "S4_S4") (pintype "passive"))
      (node (ref "U$10") (pin "GNDIN") (pinfunction "GNDIN_GNDIN") (pintype "power_in"))
      (node (ref "U$10") (pin "GNDOUT") (pinfunction "GNDOUT_GNDOUT") (pintype "power_in"))
      (node (ref "U$27") (pin "2") (pinfunction "GND_2") (pintype "power_in"))
      (node (ref "U1") (pin "2") (pinfunction "GND_2") (pintype "bidirectional"))
      (node (ref "U3") (pin "1") (pinfunction "GND_1") (pintype "bidirectional"))
      (node (ref "USB") (pin "GND") (pinfunction "GND_GND") (pintype "bidirectional"))
      (node (ref "USB") (pin "MT1") (pinfunction "GND_MT1") (pintype "bidirectional"))
      (node (ref "USB") (pin "MT2") (pinfunction "GND_MT2") (pintype "bidirectional"))
      (node (ref "X1") (pin "13") (pinfunction "1_13") (pintype "passive"))
      (node (ref "X1") (pin "14") (pinfunction "1_14") (pintype "passive"))
      (node (ref "X1") (pin "21") (pinfunction "1_21") (pintype "passive"))
      (node (ref "X1") (pin "22") (pinfunction "1_22") (pintype "passive"))
      (node (ref "X1") (pin "23") (pinfunction "1_23") (pintype "passive"))
      (node (ref "X1") (pin "29") (pinfunction "1_29") (pintype "passive"))
      (node (ref "X1") (pin "3") (pinfunction "1_3") (pintype "passive"))
      (node (ref "X1") (pin "36") (pinfunction "1_36") (pintype "passive"))
      (node (ref "X1") (pin "5") (pinfunction "1_5") (pintype "passive"))
      (node (ref "X1") (pin "6") (pinfunction "1_6") (pintype "passive"))
      (node (ref "X1") (pin "7") (pinfunction "1_7") (pintype "passive"))
    )
    (net (code "66") (name "Net-(L+-P)") (class "Default")
      (node (ref "L+") (pin "1") (pinfunction "P_1") (pintype "passive"))
      (node (ref "PAM1") (pin "1") (pinfunction "+OUT_L_1") (pintype "input"))
    )
    (net (code "67") (name "Net-(L--P)") (class "Default")
      (node (ref "L-") (pin "1") (pinfunction "P_1") (pintype "passive"))
      (node (ref "PAM1") (pin "3") (pinfunction "-OUT_L_3") (pintype "input"))
    )
    (net (code "68") (name "Net-(L1-1)") (class "Default")
      (node (ref "D1") (pin "A") (pinfunction "A_A") (pintype "bidirectional"))
      (node (ref "D2") (pin "A") (pinfunction "A_A") (pintype "bidirectional"))
      (node (ref "L1") (pin "P$1") (pinfunction "1_P$1") (pintype "passive"))
      (node (ref "L2") (pin "P$1") (pinfunction "1_P$1") (pintype "passive"))
      (node (ref "U$27") (pin "1") (pinfunction "SW_1") (pintype "power_in"))
      (node (ref "U1") (pin "1") (pinfunction "SW_1") (pintype "bidirectional"))
    )
    (net (code "69") (name "Net-(LI-P)") (class "Default")
      (node (ref "C14") (pin "1") (pinfunction "1_1") (pintype "passive"))
      (node (ref "LI") (pin "1") (pinfunction "P_1") (pintype "passive"))
      (node (ref "LO") (pin "1") (pinfunction "P_1") (pintype "passive"))
      (node (ref "R4") (pin "1") (pinfunction "1_1") (pintype "passive"))
    )
    (net (code "70") (name "Net-(PAM1-+OUT_R)") (class "Default")
      (node (ref "PAM1") (pin "16") (pinfunction "+OUT_R_16") (pintype "output"))
      (node (ref "R+") (pin "1") (pinfunction "P_1") (pintype "passive"))
    )
    (net (code "71") (name "Net-(PAM1--OUT_R)") (class "Default")
      (node (ref "PAM1") (pin "14") (pinfunction "-OUT_R_14") (pintype "output"))
      (node (ref "R-") (pin "1") (pinfunction "P_1") (pintype "passive"))
    )
    (net (code "72") (name "Net-(PAM1-INL)") (class "Default")
      (node (ref "C14") (pin "2") (pinfunction "2_2") (pintype "passive"))
      (node (ref "PAM1") (pin "7") (pinfunction "INL_7") (pintype "input"))
    )
    (net (code "73") (name "Net-(PAM1-INR)") (class "Default")
      (node (ref "C13") (pin "2") (pinfunction "2_2") (pintype "passive"))
      (node (ref "PAM1") (pin "10") (pinfunction "INR_10") (pintype "output"))
    )
    (net (code "74") (name "Net-(PAM1-SHND)") (class "Default")
      (node (ref "J1") (pin "XIO-P4") (pinfunction "XIO-P4_XIO-P4") (pintype "passive"))
      (node (ref "PAM1") (pin "12") (pinfunction "SHND_12") (pintype "output"))
      (node (ref "R6") (pin "2") (pinfunction "2_2") (pintype "passive"))
    )
    (net (code "75") (name "Net-(PAM1-VREF)") (class "Default")
      (node (ref "C6") (pin "1") (pinfunction "1_1") (pintype "passive"))
      (node (ref "PAM1") (pin "8") (pinfunction "VREF_8") (pintype "input"))
    )
    (net (code "76") (name "Net-(PV-P)") (class "Default")
      (node (ref "PV") (pin "1") (pinfunction "P_1") (pintype "passive"))
      (node (ref "U$10") (pin "VIN") (pinfunction "VIN_VIN") (pintype "power_in"))
    )
    (net (code "77") (name "Net-(RI-P)") (class "Default")
      (node (ref "C13") (pin "1") (pinfunction "1_1") (pintype "passive"))
      (node (ref "R5") (pin "1") (pinfunction "1_1") (pintype "passive"))
      (node (ref "RI") (pin "1") (pinfunction "P_1") (pintype "passive"))
      (node (ref "RO") (pin "1") (pinfunction "P_1") (pintype "passive"))
    )
    (net (code "78") (name "VCC3V3") (class "Default")
      (node (ref "C9") (pin "1") (pinfunction "1_1") (pintype "passive"))
      (node (ref "J1") (pin "VCC3V3") (pinfunction "VCC3V3_VCC3V3") (pintype "power_in"))
      (node (ref "R12") (pin "2") (pinfunction "2_2") (pintype "passive"))
      (node (ref "SDIO") (pin "4") (pinfunction "VDD_4") (pintype "power_in"))
      (node (ref "SJ3") (pin "1") (pinfunction "1_1") (pintype "passive"))
    )
    (net (code "79") (name "VCC5V") (class "Default")
      (node (ref "C10") (pin "1") (pinfunction "1_1") (pintype "passive"))
      (node (ref "C7") (pin "1") (pinfunction "1_1") (pintype "passive"))
      (node (ref "J1") (pin "VCC5V@1") (pinfunction "VCC-5V_VCC5V@1") (pintype "power_in"))
      (node (ref "SJ1") (pin "1") (pinfunction "1_1") (pintype "passive"))
      (node (ref "SJ3") (pin "3") (pinfunction "3_3") (pintype "passive"))
    )
    (net (code "80") (name "unconnected-(J1-PadAP-EINT1)") (class "Default")
      (node (ref "J1") (pin "AP-EINT1") (pinfunction "AP-EINT1_AP-EINT1") (pintype "passive"))
    )
    (net (code "81") (name "unconnected-(J1-PadCSID6)") (class "Default")
      (node (ref "J1") (pin "CSID6") (pinfunction "CSID6_CSID6") (pintype "passive"))
    )
    (net (code "82") (name "unconnected-(J1-PadCSID7)") (class "Default")
      (node (ref "J1") (pin "CSID7") (pinfunction "CSID7_CSID7") (pintype "passive"))
    )
    (net (code "83") (name "unconnected-(J1-PadMICIN1)") (class "Default")
      (node (ref "J1") (pin "MICIN1") (pinfunction "MICIN1_MICIN1") (pintype "passive"))
    )
    (net (code "84") (name "unconnected-(J1-PadMICM)") (class "Default")
      (node (ref "J1") (pin "MICM") (pinfunction "MICM_MICM") (pintype "passive"))
    )
    (net (code "85") (name "unconnected-(J1-PadTS)") (class "Default")
      (node (ref "J1") (pin "TS") (pinfunction "TS_TS") (pintype "passive"))
    )
    (net (code "86") (name "unconnected-(J1-PadXIO-P0)") (class "Default")
      (node (ref "J1") (pin "XIO-P0") (pinfunction "XIO-P0_XIO-P0") (pintype "passive"))
    )
    (net (code "87") (name "unconnected-(J1-PadXIO-P1)") (class "Default")
      (node (ref "J1") (pin "XIO-P1") (pinfunction "XIO-P1_XIO-P1") (pintype "passive"))
    )
    (net (code "88") (name "unconnected-(U3-NC-Pad3)") (class "Default")
      (node (ref "U3") (pin "3") (pinfunction "NC_3") (pintype "bidirectional"))
    )
    (net (code "89") (name "unconnected-(U3-NC-Pad4)") (class "Default")
      (node (ref "U3") (pin "4") (pinfunction "NC_4") (pintype "bidirectional"))
    )
    (net (code "90") (name "unconnected-(U3-NC-Pad5)") (class "Default")
      (node (ref "U3") (pin "5") (pinfunction "NC_5") (pintype "bidirectional"))
    )
    (net (code "91") (name "unconnected-(U3-NC-Pad6)") (class "Default")
      (node (ref "U3") (pin "6") (pinfunction "NC_6") (pintype "bidirectional"))
    )
    (net (code "92") (name "unconnected-(USB-PadD+)") (class "Default")
      (node (ref "USB") (pin "D+") (pinfunction "D+_D+") (pintype "bidirectional"))
    )
    (net (code "93") (name "unconnected-(USB-PadD-)") (class "Default")
      (node (ref "USB") (pin "D-") (pinfunction "D-_D-") (pintype "bidirectional"))
    )
    (net (code "94") (name "unconnected-(X1AC-1-Pad35)") (class "Default")
      (node (ref "X1") (pin "35") (pinfunction "1_35") (pintype "passive"))
    )
  )
)
